# 2_STM32F107.net
KiCad netlist of a schematic drawn in Altium Designer
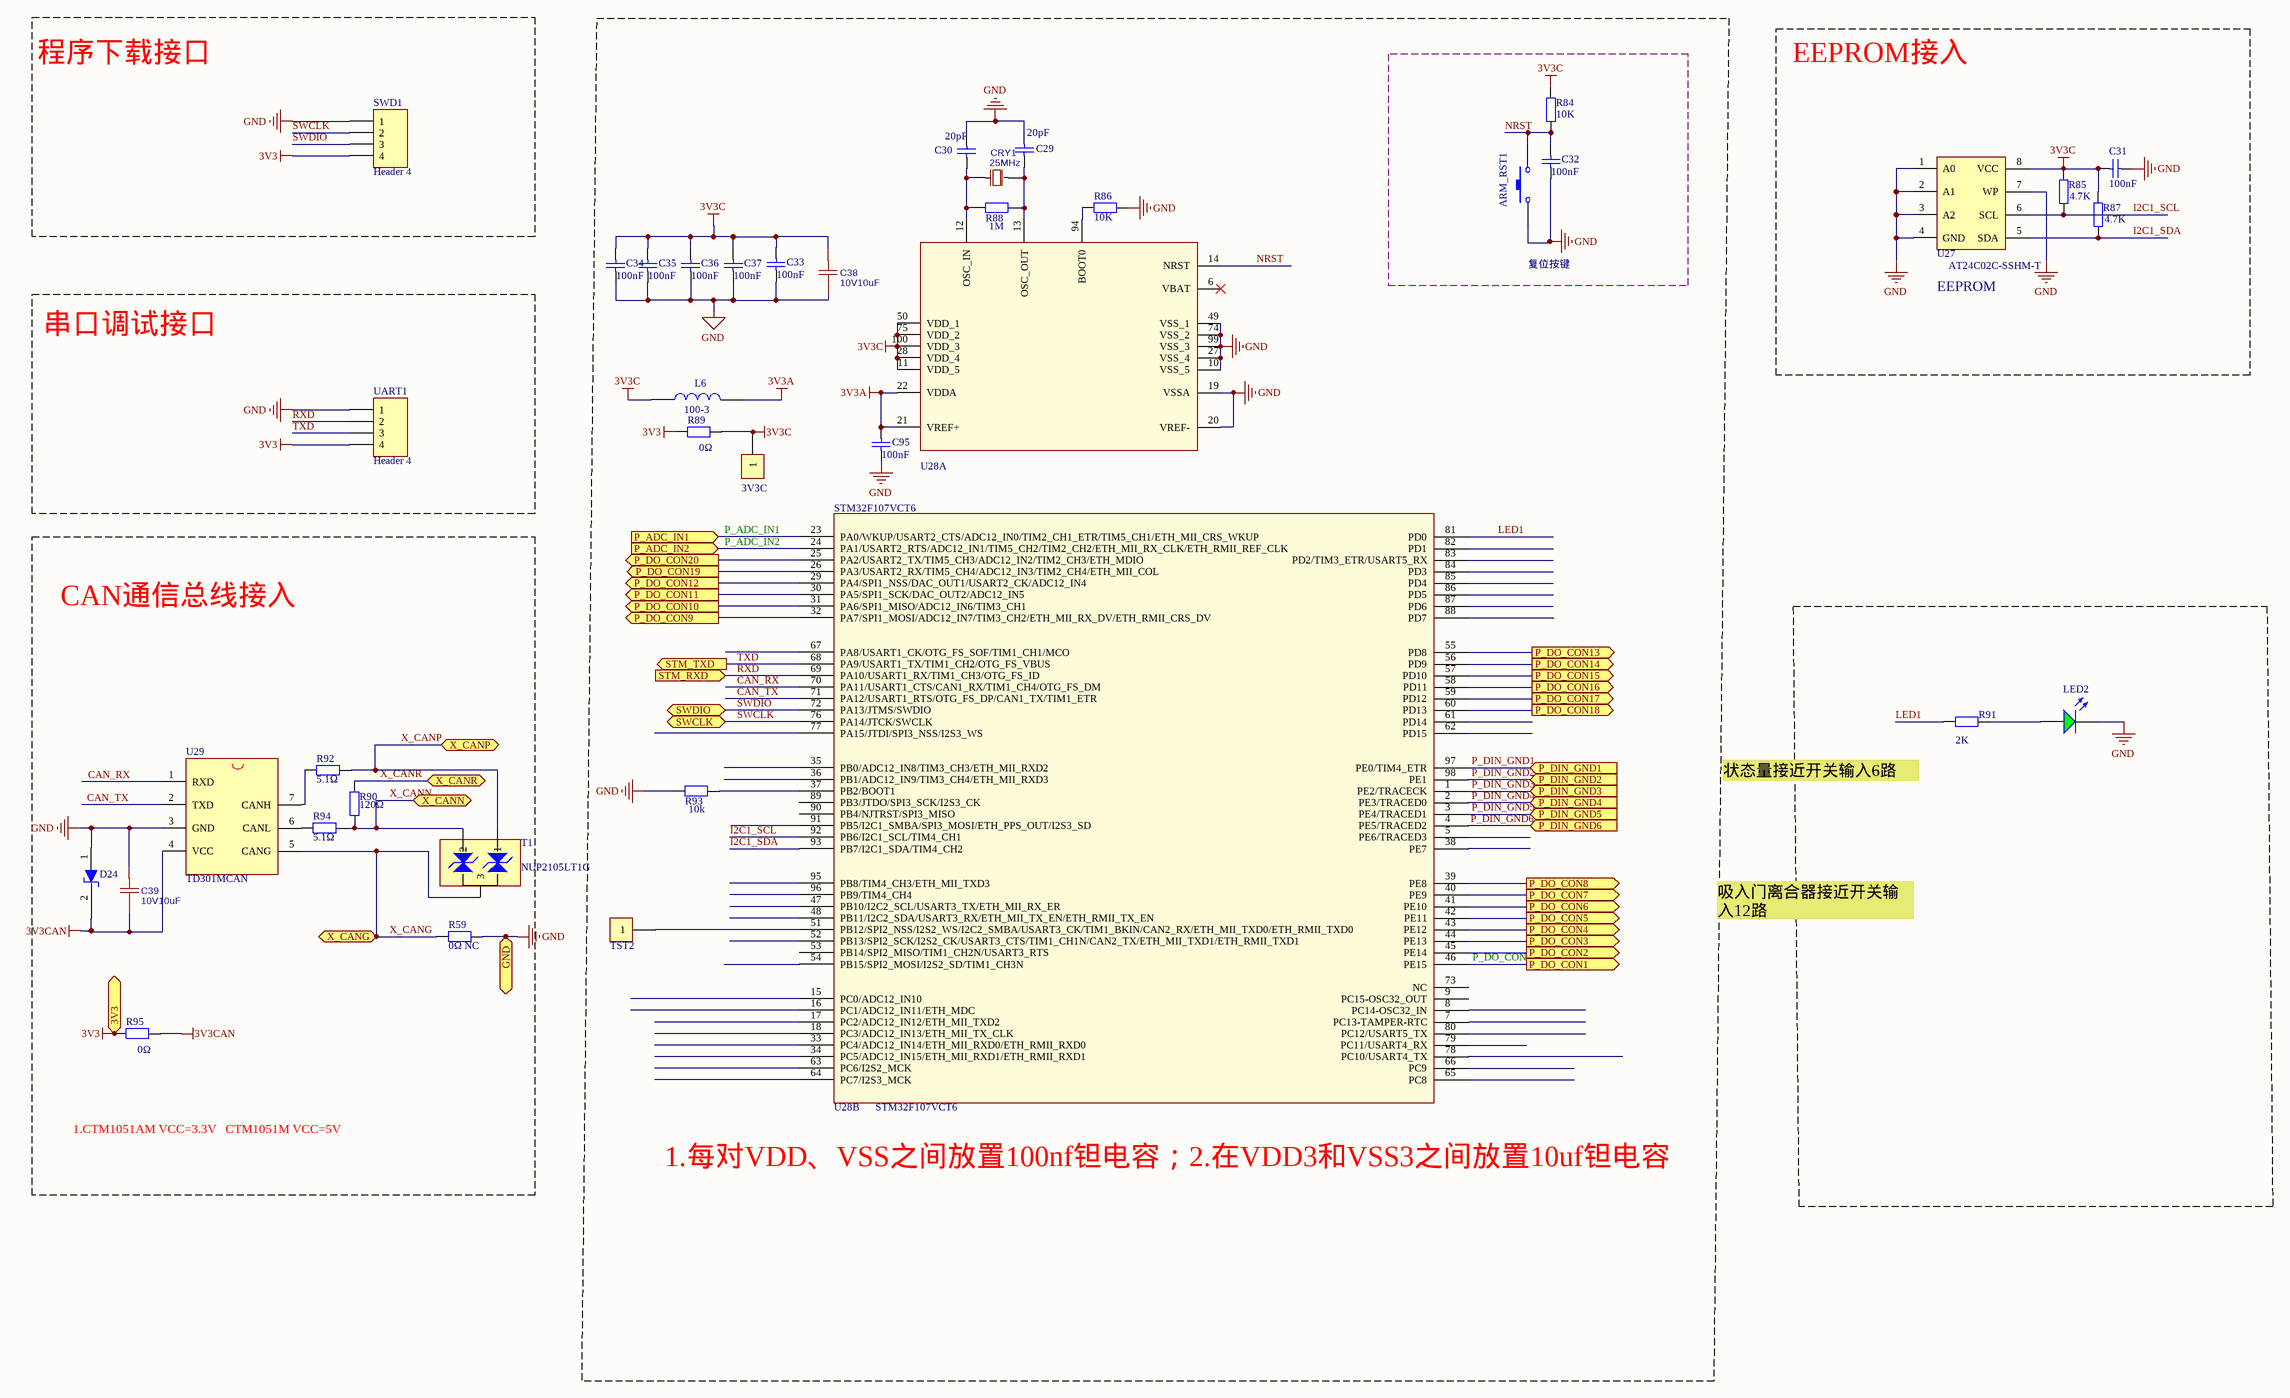
[diagram p0: 2.STM32F107.SchDoc]

(export (version "E")
  (design (tool "Eeschema 10.0.6"))
  (components
    (comp (ref "3V3C")
      (value "TST3V3C")
      (footprint "Con-TEST-VCC")
      (description "Connector")
      (libsource (lib "*") (part "CON1"))
    )
    (comp (ref "ARM_RST1")
      (value "button")
      (footprint "SW_PB2_A1")
      (description "轻触开关3.6*6.1*2.5")
      (libsource (lib "SUPERWDS") (part "button"))
    )
    (comp (ref "C29")
      (value "20pF")
      (footprint "C0603-M")
      (description "Capacitor")
      (fields (field (name "PUBLISHER") "Altium Limited"))
      (libsource (lib "SUPERWDS") (part "Cap1"))
    )
    (comp (ref "C30")
      (value "20pF")
      (footprint "C0603-M")
      (description "Capacitor")
      (fields (field (name "PUBLISHER") "Altium Limited"))
      (libsource (lib "SUPERWDS") (part "Cap1"))
    )
    (comp (ref "C31")
      (value "100nF")
      (footprint "C0603-M")
      (description "Capacitor")
      (fields (field (name "PUBLISHER") "Altium Limited"))
      (libsource (lib "SUPERWDS") (part "Cap1"))
    )
    (comp (ref "C32")
      (value "100nF")
      (footprint "C0603-M")
      (description "Capacitor")
      (fields (field (name "PUBLISHER") "Altium Limited"))
      (libsource (lib "SUPERWDS") (part "Cap1"))
    )
    (comp (ref "C33")
      (value "100nF")
      (footprint "C0603-M")
      (description "Capacitor")
      (fields (field (name "PUBLISHER") "Altium Limited"))
      (libsource (lib "SUPERWDS") (part "Cap1"))
    )
    (comp (ref "C34")
      (value "100nF")
      (footprint "C0603-M")
      (description "Capacitor")
      (fields (field (name "PUBLISHER") "Altium Limited"))
      (libsource (lib "SUPERWDS") (part "Cap1"))
    )
    (comp (ref "C35")
      (value "100nF")
      (footprint "C0603-M")
      (description "Capacitor")
      (fields (field (name "PUBLISHER") "Altium Limited"))
      (libsource (lib "SUPERWDS") (part "Cap1"))
    )
    (comp (ref "C36")
      (value "100nF")
      (footprint "C0603-M")
      (description "Capacitor")
      (fields (field (name "PUBLISHER") "Altium Limited"))
      (libsource (lib "SUPERWDS") (part "Cap1"))
    )
    (comp (ref "C37")
      (value "100nF")
      (footprint "C0603-M")
      (description "Capacitor")
      (fields (field (name "PUBLISHER") "Altium Limited"))
      (libsource (lib "SUPERWDS") (part "Cap1"))
    )
    (comp (ref "C38")
      (value "10V10uF")
      (footprint "C0603-M")
      (description "贴片电容")
      (fields
        (field (name "BOM_MANUFACTURER PART") "CL10A106KP8NNNC")
        (field (name "BOM_SUPPLIER PART") "C19702")
      )
      (libsource (lib "altium-import") (part "root_1_10uF_"))
    )
    (comp (ref "C39")
      (value "10V10uF")
      (footprint "C0603-M")
      (description "贴片电容")
      (fields
        (field (name "BOM_MANUFACTURER PART") "CL10A106KP8NNNC")
        (field (name "BOM_SUPPLIER PART") "C19702")
      )
      (libsource (lib "altium-import") (part "root_1_10uF_"))
    )
    (comp (ref "C95")
      (value "100nF")
      (footprint "C0603-M")
      (description "Capacitor")
      (fields (field (name "PUBLISHER") "Altium Limited"))
      (libsource (lib "SUPERWDS") (part "Cap1"))
    )
    (comp (ref "CRY1")
      (value "25MHz")
      (footprint "CRYSTAL-SMD_L11.5-W4.8-LS12.7")
      (fields
        (field (name "BOM_MANUFACTURER PART") "X49SM25MSD2SC")
        (field (name "BOM_SUPPLIER PART") "C14872")
      )
      (libsource (lib "altium-import") (part "root_0_25MHz_"))
    )
    (comp (ref "D24")
      (value "P6SMB6.8CA")
      (footprint "LC-SMA(DO-214AC)_S2")
      (description "TVS二极管/P6SMB6.8CA")
      (libsource (lib "自动对行") (part "TVS"))
    )
    (comp (ref "L6")
      (value "100-3")
      (footprint "L0805-M")
      (description "贴片磁珠/100Ω 3A/0805")
      (libsource (lib "*") (part "INDUCTOR"))
    )
    (comp (ref "LED2")
      (value "绿灯 0603")
      (footprint "0603_LED_S1")
      (description "发光二极管")
      (libsource (lib "Miscellaneous Devices LC") (part "0603 绿灯"))
    )
    (comp (ref "R59")
      (value "0Ω NC")
      (footprint "R0603-M")
      (description "Resistor")
      (fields (field (name "PUBLISHER") "Altium Limited"))
      (libsource (lib "") (part "Res2_3"))
    )
    (comp (ref "R84")
      (value "10K")
      (footprint "R0603-M")
      (description "Resistor")
      (fields (field (name "PUBLISHER") "Altium Limited"))
      (libsource (lib "SUPERWDS") (part "RES"))
    )
    (comp (ref "R85")
      (value "4.7K")
      (footprint "R0603-M")
      (description "Resistor")
      (fields (field (name "PUBLISHER") "Altium Limited"))
      (libsource (lib "SUPERWDS") (part "RES"))
    )
    (comp (ref "R86")
      (value "10K")
      (footprint "R0603-M")
      (description "Resistor")
      (fields (field (name "PUBLISHER") "Altium Limited"))
      (libsource (lib "") (part "RES_1"))
    )
    (comp (ref "R87")
      (value "4.7K")
      (footprint "R0603-M")
      (description "Resistor")
      (fields (field (name "PUBLISHER") "Altium Limited"))
      (libsource (lib "SUPERWDS") (part "RES"))
    )
    (comp (ref "R88")
      (value "1M")
      (footprint "R0603-M")
      (description "Resistor")
      (fields (field (name "PUBLISHER") "Altium Limited"))
      (libsource (lib "") (part "RES_1"))
    )
    (comp (ref "R89")
      (value "0Ω")
      (footprint "R0603-M")
      (description "Resistor")
      (fields (field (name "PUBLISHER") "Altium Limited"))
      (libsource (lib "") (part "Res2_1"))
    )
    (comp (ref "R90")
      (value "120Ω")
      (footprint "R0603-M")
      (description "贴片电阻/120Ω")
      (fields (field (name "PUBLISHER") "Altium Limited"))
      (libsource (lib "Miscellaneous Devices") (part "Res2"))
    )
    (comp (ref "R91")
      (value "2K")
      (footprint "R0603-M")
      (description "Resistor")
      (fields (field (name "PUBLISHER") "Altium Limited"))
      (libsource (lib "") (part "RES_2"))
    )
    (comp (ref "R92")
      (value "5.1Ω")
      (footprint "R0603-M")
      (description "贴片电阻/120Ω")
      (fields (field (name "PUBLISHER") "Altium Limited"))
      (libsource (lib "") (part "Res2_2"))
    )
    (comp (ref "R93")
      (value "10k")
      (footprint "R0603-M")
      (description "Resistor")
      (fields (field (name "PUBLISHER") "Altium Limited"))
      (libsource (lib "") (part "RES_1"))
    )
    (comp (ref "R94")
      (value "5.1Ω")
      (footprint "R0603-M")
      (description "贴片电阻/120Ω")
      (fields (field (name "PUBLISHER") "Altium Limited"))
      (libsource (lib "") (part "Res2_2"))
    )
    (comp (ref "R95")
      (value "0Ω")
      (footprint "R0603-M")
      (description "Resistor")
      (fields (field (name "PUBLISHER") "Altium Limited"))
      (libsource (lib "") (part "Res2_1"))
    )
    (comp (ref "SWD1")
      (value "Header 4")
      (footprint "HDR1X4")
      (description "Header, 4-Pin")
      (fields (field (name "PUBLISHER") "Altium Limited"))
      (libsource (lib "Miscellaneous Connectors") (part "Header 4"))
    )
    (comp (ref "T1")
      (value "NUP2105LT1G")
      (footprint "LC-SOT-23(SOT-23-3)")
      (description "TVS")
      (libsource (lib "motorCtr1") (part "TVS2"))
    )
    (comp (ref "TST2")
      (value "TST3V3A")
      (footprint "Con-TEST-VCC")
      (description "Connector")
      (libsource (lib "") (part "CON1_1"))
    )
    (comp (ref "U27")
      (value "AT24C02C-SSHM-T")
      (footprint "SO-8")
      (description "EEPROM")
      (libsource (lib "SUPERWDS") (part "AT24LC02"))
    )
    (comp (ref "U28")
      (value "STM32F107VCT6")
      (footprint "myPcb:LQFP100")
      (fields (field (name "ALTIUM_VALUE") "STM32F107VCT6"))
      (libsource (lib "SUPERWDS") (part "STM32F107"))
    )
    (comp (ref "U29")
      (value "TD301MCAN")
      (footprint "LC-DIP-8")
      (description "隔离CAN收发器CTM1051AM或TD301MCAN")
      (libsource (lib "YYGB") (part "CTM1051AM"))
    )
    (comp (ref "UART1")
      (value "Header 4")
      (footprint "HDR1X4")
      (description "Header, 4-Pin")
      (fields (field (name "PUBLISHER") "Altium Limited"))
      (libsource (lib "Miscellaneous Connectors") (part "Header 4"))
    )
  )
  (nets
    (net (code "2") (name "/CAN_RX") (class "Default")
      (node (ref "U28") (pin "70") (pinfunction "PA11/USART1_CTS/CAN1_RX/TIM1_CH4/OTG_FS_DM_70") (pintype "passive"))
      (node (ref "U29") (pin "1") (pinfunction "RXD_1") (pintype "passive"))
    )
    (net (code "3") (name "/CAN_TX") (class "Default")
      (node (ref "U28") (pin "71") (pinfunction "PA12/USART1_RTS/OTG_FS_DP/CAN1_TX/TIM1_ETR_71") (pintype "passive"))
      (node (ref "U29") (pin "2") (pinfunction "TXD_2") (pintype "passive"))
    )
    (net (code "4") (name "/I2C1_SCL") (class "Default")
      (node (ref "R85") (pin "1") (pinfunction "1_1") (pintype "passive"))
      (node (ref "U27") (pin "6") (pinfunction "SCL_6") (pintype "passive"))
      (node (ref "U28") (pin "92") (pinfunction "PB6/I2C1_SCL/TIM4_CH1_92") (pintype "passive"))
    )
    (net (code "5") (name "/I2C1_SDA") (class "Default")
      (node (ref "R87") (pin "1") (pinfunction "1_1") (pintype "passive"))
      (node (ref "U27") (pin "5") (pinfunction "SDA_5") (pintype "passive"))
      (node (ref "U28") (pin "93") (pinfunction "PB7/I2C1_SDA/TIM4_CH2_93") (pintype "passive"))
    )
    (net (code "6") (name "/LED1") (class "Default")
      (node (ref "R91") (pin "1") (pinfunction "1_1") (pintype "passive"))
      (node (ref "U28") (pin "81") (pinfunction "PD0_81") (pintype "passive"))
    )
    (net (code "7") (name "/NRST") (class "Default")
      (node (ref "ARM_RST1") (pin "2") (pinfunction "2_2") (pintype "passive"))
      (node (ref "C32") (pin "2") (pinfunction "2_2") (pintype "passive"))
      (node (ref "R84") (pin "1") (pinfunction "1_1") (pintype "passive"))
      (node (ref "U28") (pin "14") (pinfunction "NRST_14") (pintype "passive"))
    )
    (net (code "8") (name "/P_ADC_IN1") (class "Default")
      (node (ref "U28") (pin "23") (pinfunction "PA0/WKUP/USART2_CTS/ADC12_IN0/TIM2_CH1_ETR/TIM5_CH1/ETH_MII_CRS_WKUP_23") (pintype "passive"))
    )
    (net (code "9") (name "/P_ADC_IN2") (class "Default")
      (node (ref "U28") (pin "24") (pinfunction "PA1/USART2_RTS/ADC12_IN1/TIM5_CH2/TIM2_CH2/ETH_MII_RX_CLK/ETH_RMII_REF_CLK_24") (pintype "passive"))
    )
    (net (code "10") (name "/P_DIN_GND1") (class "Default")
      (node (ref "U28") (pin "97") (pinfunction "PE0/TIM4_ETR_97") (pintype "passive"))
    )
    (net (code "11") (name "/P_DIN_GND2") (class "Default")
      (node (ref "U28") (pin "98") (pinfunction "PE1_98") (pintype "passive"))
    )
    (net (code "12") (name "/P_DIN_GND3") (class "Default")
      (node (ref "U28") (pin "1") (pinfunction "PE2/TRACECK_1") (pintype "passive"))
    )
    (net (code "13") (name "/P_DIN_GND4") (class "Default")
      (node (ref "U28") (pin "2") (pinfunction "PE3/TRACED0_2") (pintype "passive"))
    )
    (net (code "14") (name "/P_DIN_GND5") (class "Default")
      (node (ref "U28") (pin "3") (pinfunction "PE4/TRACED1_3") (pintype "passive"))
    )
    (net (code "15") (name "/P_DIN_GND6") (class "Default")
      (node (ref "U28") (pin "4") (pinfunction "PE5/TRACED2_4") (pintype "passive"))
    )
    (net (code "16") (name "/P_DO_CON1") (class "Default")
      (node (ref "U28") (pin "46") (pinfunction "PE15_46") (pintype "passive"))
    )
    (net (code "17") (name "/P_DO_CON2") (class "Default")
      (node (ref "U28") (pin "45") (pinfunction "PE14_45") (pintype "passive"))
    )
    (net (code "18") (name "/P_DO_CON3") (class "Default")
      (node (ref "U28") (pin "44") (pinfunction "PE13_44") (pintype "passive"))
    )
    (net (code "19") (name "/P_DO_CON4") (class "Default")
      (node (ref "U28") (pin "43") (pinfunction "PE12_43") (pintype "passive"))
    )
    (net (code "20") (name "/P_DO_CON5") (class "Default")
      (node (ref "U28") (pin "42") (pinfunction "PE11_42") (pintype "passive"))
    )
    (net (code "21") (name "/P_DO_CON6") (class "Default")
      (node (ref "U28") (pin "41") (pinfunction "PE10_41") (pintype "passive"))
    )
    (net (code "22") (name "/P_DO_CON7") (class "Default")
      (node (ref "U28") (pin "40") (pinfunction "PE9_40") (pintype "passive"))
    )
    (net (code "23") (name "/P_DO_CON8") (class "Default")
      (node (ref "U28") (pin "39") (pinfunction "PE8_39") (pintype "passive"))
    )
    (net (code "24") (name "/P_DO_CON9") (class "Default")
      (node (ref "U28") (pin "32") (pinfunction "PA7/SPI1_MOSI/ADC12_IN7/TIM3_CH2/ETH_MII_RX_DV/ETH_RMII_CRS_DV_32") (pintype "passive"))
    )
    (net (code "25") (name "/P_DO_CON10") (class "Default")
      (node (ref "U28") (pin "31") (pinfunction "PA6/SPI1_MISO/ADC12_IN6/TIM3_CH1_31") (pintype "passive"))
    )
    (net (code "26") (name "/P_DO_CON11") (class "Default")
      (node (ref "U28") (pin "30") (pinfunction "PA5/SPI1_SCK/DAC_OUT2/ADC12_IN5_30") (pintype "passive"))
    )
    (net (code "27") (name "/P_DO_CON12") (class "Default")
      (node (ref "U28") (pin "29") (pinfunction "PA4/SPI1_NSS/DAC_OUT1/USART2_CK/ADC12_IN4_29") (pintype "passive"))
    )
    (net (code "28") (name "/P_DO_CON13") (class "Default")
      (node (ref "U28") (pin "55") (pinfunction "PD8_55") (pintype "passive"))
    )
    (net (code "29") (name "/P_DO_CON14") (class "Default")
      (node (ref "U28") (pin "56") (pinfunction "PD9_56") (pintype "passive"))
    )
    (net (code "30") (name "/P_DO_CON15") (class "Default")
      (node (ref "U28") (pin "57") (pinfunction "PD10_57") (pintype "passive"))
    )
    (net (code "31") (name "/P_DO_CON16") (class "Default")
      (node (ref "U28") (pin "58") (pinfunction "PD11_58") (pintype "passive"))
    )
    (net (code "32") (name "/P_DO_CON17") (class "Default")
      (node (ref "U28") (pin "59") (pinfunction "PD12_59") (pintype "passive"))
    )
    (net (code "33") (name "/P_DO_CON18") (class "Default")
      (node (ref "U28") (pin "60") (pinfunction "PD13_60") (pintype "passive"))
    )
    (net (code "34") (name "/P_DO_CON19") (class "Default")
      (node (ref "U28") (pin "26") (pinfunction "PA3/USART2_RX/TIM5_CH4/ADC12_IN3/TIM2_CH4/ETH_MII_COL_26") (pintype "passive"))
    )
    (net (code "35") (name "/P_DO_CON20") (class "Default")
      (node (ref "U28") (pin "25") (pinfunction "PA2/USART2_TX/TIM5_CH3/ADC12_IN2/TIM2_CH3/ETH_MDIO_25") (pintype "passive"))
    )
    (net (code "36") (name "/RXD") (class "Default")
      (node (ref "U28") (pin "69") (pinfunction "PA10/USART1_RX/TIM1_CH3/OTG_FS_ID_69") (pintype "passive"))
      (node (ref "UART1") (pin "2") (pinfunction "2_2") (pintype "passive"))
    )
    (net (code "37") (name "/SWCLK") (class "Default")
      (node (ref "SWD1") (pin "2") (pinfunction "2_2") (pintype "passive"))
      (node (ref "U28") (pin "76") (pinfunction "PA14/JTCK/SWCLK_76") (pintype "passive"))
    )
    (net (code "38") (name "/SWDIO") (class "Default")
      (node (ref "SWD1") (pin "3") (pinfunction "3_3") (pintype "passive"))
      (node (ref "U28") (pin "72") (pinfunction "PA13/JTMS/SWDIO_72") (pintype "passive"))
    )
    (net (code "39") (name "/TXD") (class "Default")
      (node (ref "U28") (pin "68") (pinfunction "PA9/USART1_TX/TIM1_CH2/OTG_FS_VBUS_68") (pintype "passive"))
      (node (ref "UART1") (pin "3") (pinfunction "3_3") (pintype "passive"))
    )
    (net (code "40") (name "/X_CANG") (class "Default")
      (node (ref "R59") (pin "2") (pinfunction "2_2") (pintype "passive"))
      (node (ref "T1") (pin "3") (pinfunction "3_3") (pintype "passive"))
      (node (ref "U29") (pin "5") (pinfunction "CANG_5") (pintype "passive"))
    )
    (net (code "41") (name "/X_CANN") (class "Default")
      (node (ref "R90") (pin "2") (pinfunction "2_2") (pintype "passive"))
      (node (ref "R94") (pin "1") (pinfunction "1_1") (pintype "passive"))
      (node (ref "T1") (pin "2") (pinfunction "2_2") (pintype "passive"))
    )
    (net (code "42") (name "/X_CANP") (class "Default")
      (node (ref "R92") (pin "1") (pinfunction "1_1") (pintype "passive"))
      (node (ref "T1") (pin "1") (pinfunction "1_1") (pintype "passive"))
    )
    (net (code "43") (name "/X_CANR") (class "Default")
      (node (ref "R90") (pin "1") (pinfunction "1_1") (pintype "passive"))
    )
    (net (code "44") (name "3V3") (class "Default")
      (node (ref "R89") (pin "1") (pinfunction "1_1") (pintype "passive"))
      (node (ref "R95") (pin "1") (pinfunction "1_1") (pintype "passive"))
      (node (ref "SWD1") (pin "4") (pinfunction "4_4") (pintype "passive"))
      (node (ref "UART1") (pin "4") (pinfunction "4_4") (pintype "passive"))
    )
    (net (code "45") (name "3V3A") (class "Default")
      (node (ref "C95") (pin "2") (pinfunction "2_2") (pintype "passive"))
      (node (ref "L6") (pin "2") (pinfunction "2_2") (pintype "passive"))
      (node (ref "U28") (pin "21") (pinfunction "VREF+_21") (pintype "passive"))
      (node (ref "U28") (pin "22") (pinfunction "VDDA_22") (pintype "passive"))
    )
    (net (code "46") (name "3V3C") (class "Default")
      (node (ref "3V3C") (pin "1") (pinfunction "1_1") (pintype "passive"))
      (node (ref "C31") (pin "2") (pinfunction "2_2") (pintype "passive"))
      (node (ref "C33") (pin "2") (pinfunction "2_2") (pintype "passive"))
      (node (ref "C34") (pin "2") (pinfunction "2_2") (pintype "passive"))
      (node (ref "C35") (pin "2") (pinfunction "2_2") (pintype "passive"))
      (node (ref "C36") (pin "2") (pinfunction "2_2") (pintype "passive"))
      (node (ref "C37") (pin "2") (pinfunction "2_2") (pintype "passive"))
      (node (ref "C38") (pin "2") (pinfunction "2_2") (pintype "passive"))
      (node (ref "L6") (pin "1") (pinfunction "1_1") (pintype "passive"))
      (node (ref "R84") (pin "2") (pinfunction "2_2") (pintype "passive"))
      (node (ref "R85") (pin "2") (pinfunction "2_2") (pintype "passive"))
      (node (ref "R87") (pin "2") (pinfunction "2_2") (pintype "passive"))
      (node (ref "R89") (pin "2") (pinfunction "2_2") (pintype "passive"))
      (node (ref "U27") (pin "8") (pinfunction "VCC_8") (pintype "passive"))
      (node (ref "U28") (pin "100") (pinfunction "VDD_3_100") (pintype "passive"))
      (node (ref "U28") (pin "11") (pinfunction "VDD_5_11") (pintype "passive"))
      (node (ref "U28") (pin "28") (pinfunction "VDD_4_28") (pintype "passive"))
      (node (ref "U28") (pin "50") (pinfunction "VDD_1_50") (pintype "passive"))
      (node (ref "U28") (pin "75") (pinfunction "VDD_2_75") (pintype "passive"))
    )
    (net (code "47") (name "3V3CAN") (class "Default")
      (node (ref "C39") (pin "1") (pinfunction "1_1") (pintype "passive"))
      (node (ref "D24") (pin "2") (pinfunction "2_2") (pintype "passive"))
      (node (ref "R95") (pin "2") (pinfunction "2_2") (pintype "passive"))
      (node (ref "U29") (pin "4") (pinfunction "VCC_4") (pintype "passive"))
    )
    (net (code "48") (name "GND") (class "Default")
      (node (ref "ARM_RST1") (pin "1") (pinfunction "1_1") (pintype "passive"))
      (node (ref "C29") (pin "1") (pinfunction "1_1") (pintype "passive"))
      (node (ref "C30") (pin "2") (pinfunction "2_2") (pintype "passive"))
      (node (ref "C31") (pin "1") (pinfunction "1_1") (pintype "passive"))
      (node (ref "C32") (pin "1") (pinfunction "1_1") (pintype "passive"))
      (node (ref "C33") (pin "1") (pinfunction "1_1") (pintype "passive"))
      (node (ref "C34") (pin "1") (pinfunction "1_1") (pintype "passive"))
      (node (ref "C35") (pin "1") (pinfunction "1_1") (pintype "passive"))
      (node (ref "C36") (pin "1") (pinfunction "1_1") (pintype "passive"))
      (node (ref "C37") (pin "1") (pinfunction "1_1") (pintype "passive"))
      (node (ref "C38") (pin "1") (pinfunction "1_1") (pintype "passive"))
      (node (ref "C39") (pin "2") (pinfunction "2_2") (pintype "passive"))
      (node (ref "C95") (pin "1") (pinfunction "1_1") (pintype "passive"))
      (node (ref "D24") (pin "1") (pinfunction "1_1") (pintype "passive"))
      (node (ref "LED2") (pin "K") (pinfunction "K_K") (pintype "passive"))
      (node (ref "R59") (pin "1") (pinfunction "1_1") (pintype "passive"))
      (node (ref "R86") (pin "1") (pinfunction "1_1") (pintype "passive"))
      (node (ref "R93") (pin "2") (pinfunction "2_2") (pintype "passive"))
      (node (ref "SWD1") (pin "1") (pinfunction "1_1") (pintype "passive"))
      (node (ref "U27") (pin "1") (pinfunction "A0_1") (pintype "passive"))
      (node (ref "U27") (pin "2") (pinfunction "A1_2") (pintype "passive"))
      (node (ref "U27") (pin "3") (pinfunction "A2_3") (pintype "passive"))
      (node (ref "U27") (pin "4") (pinfunction "GND_4") (pintype "passive"))
      (node (ref "U27") (pin "7") (pinfunction "WP_7") (pintype "passive"))
      (node (ref "U28") (pin "10") (pinfunction "VSS_5_10") (pintype "passive"))
      (node (ref "U28") (pin "19") (pinfunction "VSSA_19") (pintype "passive"))
      (node (ref "U28") (pin "20") (pinfunction "VREF-_20") (pintype "passive"))
      (node (ref "U28") (pin "27") (pinfunction "VSS_4_27") (pintype "passive"))
      (node (ref "U28") (pin "49") (pinfunction "VSS_1_49") (pintype "passive"))
      (node (ref "U28") (pin "74") (pinfunction "VSS_2_74") (pintype "passive"))
      (node (ref "U28") (pin "99") (pinfunction "VSS_3_99") (pintype "passive"))
      (node (ref "U29") (pin "3") (pinfunction "GND_3") (pintype "passive"))
      (node (ref "UART1") (pin "1") (pinfunction "1_1") (pintype "passive"))
    )
    (net (code "49") (name "Net-(CRY1-OSC1)") (class "Default")
      (node (ref "C30") (pin "1") (pinfunction "1_1") (pintype "passive"))
      (node (ref "CRY1") (pin "1") (pinfunction "OSC1_1") (pintype "passive"))
      (node (ref "R88") (pin "2") (pinfunction "2_2") (pintype "passive"))
      (node (ref "U28") (pin "12") (pinfunction "OSC_IN_12") (pintype "passive"))
    )
    (net (code "50") (name "Net-(CRY1-OSC2)") (class "Default")
      (node (ref "C29") (pin "2") (pinfunction "2_2") (pintype "passive"))
      (node (ref "CRY1") (pin "2") (pinfunction "OSC2_2") (pintype "passive"))
      (node (ref "R88") (pin "1") (pinfunction "1_1") (pintype "passive"))
      (node (ref "U28") (pin "13") (pinfunction "OSC_OUT_13") (pintype "passive"))
    )
    (net (code "51") (name "Net-(LED2-PadA)") (class "Default")
      (node (ref "LED2") (pin "A") (pinfunction "A_A") (pintype "passive"))
      (node (ref "R91") (pin "2") (pinfunction "2_2") (pintype "passive"))
    )
    (net (code "52") (name "Net-(U28A-BOOT0)") (class "Default")
      (node (ref "R86") (pin "2") (pinfunction "2_2") (pintype "passive"))
      (node (ref "U28") (pin "94") (pinfunction "BOOT0_94") (pintype "passive"))
    )
    (net (code "53") (name "Net-(U28B-PB2{slash}BOOT1)") (class "Default")
      (node (ref "R93") (pin "1") (pinfunction "1_1") (pintype "passive"))
      (node (ref "U28") (pin "37") (pinfunction "PB2/BOOT1_37") (pintype "passive"))
    )
    (net (code "54") (name "Net-(U28B-PB12{slash}SPI2_NSS{slash}I2S2_WS{slash}I2C2_SMBA{slash}USART3_CK{slash}TIM1_BKIN{slash}CAN2_RX{slash}ETH_MII_TXD0{slash}ETH_RMII_TXD0)") (class "Default")
      (node (ref "TST2") (pin "1") (pinfunction "1_1") (pintype "passive"))
      (node (ref "U28") (pin "51") (pinfunction "PB12/SPI2_NSS/I2S2_WS/I2C2_SMBA/USART3_CK/TIM1_BKIN/CAN2_RX/ETH_MII_TXD0/ETH_RMII_TXD0_51") (pintype "passive"))
    )
    (net (code "55") (name "Net-(U29-CANH)") (class "Default")
      (node (ref "R92") (pin "2") (pinfunction "2_2") (pintype "passive"))
      (node (ref "U29") (pin "7") (pinfunction "CANH_7") (pintype "passive"))
    )
    (net (code "56") (name "Net-(U29-CANL)") (class "Default")
      (node (ref "R94") (pin "2") (pinfunction "2_2") (pintype "passive"))
      (node (ref "U29") (pin "6") (pinfunction "CANL_6") (pintype "passive"))
    )
    (net (code "57") (name "unconnected-(U28A-VBAT-Pad6)") (class "Default")
      (node (ref "U28") (pin "6") (pinfunction "VBAT_6") (pintype "passive+no_connect"))
    )
    (net (code "58") (name "unconnected-(U28B-NC-Pad73)") (class "Default")
      (node (ref "U28") (pin "73") (pinfunction "NC_73") (pintype "passive"))
    )
    (net (code "59") (name "unconnected-(U28B-PA8{slash}USART1_CK{slash}OTG_FS_SOF{slash}TIM1_CH1{slash}MCO-Pad67)") (class "Default")
      (node (ref "U28") (pin "67") (pinfunction "PA8/USART1_CK/OTG_FS_SOF/TIM1_CH1/MCO_67") (pintype "passive"))
    )
    (net (code "60") (name "unconnected-(U28B-PA15{slash}JTDI{slash}SPI3_NSS{slash}I2S3_WS-Pad77)") (class "Default")
      (node (ref "U28") (pin "77") (pinfunction "PA15/JTDI/SPI3_NSS/I2S3_WS_77") (pintype "passive"))
    )
    (net (code "61") (name "unconnected-(U28B-PB0{slash}ADC12_IN8{slash}TIM3_CH3{slash}ETH_MII_RXD2-Pad35)") (class "Default")
      (node (ref "U28") (pin "35") (pinfunction "PB0/ADC12_IN8/TIM3_CH3/ETH_MII_RXD2_35") (pintype "passive"))
    )
    (net (code "62") (name "unconnected-(U28B-PB1{slash}ADC12_IN9{slash}TIM3_CH4{slash}ETH_MII_RXD3-Pad36)") (class "Default")
      (node (ref "U28") (pin "36") (pinfunction "PB1/ADC12_IN9/TIM3_CH4/ETH_MII_RXD3_36") (pintype "passive"))
    )
    (net (code "63") (name "unconnected-(U28B-PB3{slash}JTDO{slash}SPI3_SCK{slash}I2S3_CK-Pad89)") (class "Default")
      (node (ref "U28") (pin "89") (pinfunction "PB3/JTDO/SPI3_SCK/I2S3_CK_89") (pintype "passive"))
    )
    (net (code "64") (name "unconnected-(U28B-PB4{slash}NJTRST{slash}SPI3_MISO-Pad90)") (class "Default")
      (node (ref "U28") (pin "90") (pinfunction "PB4/NJTRST/SPI3_MISO_90") (pintype "passive"))
    )
    (net (code "65") (name "unconnected-(U28B-PB5{slash}I2C1_SMBA{slash}SPI3_MOSI{slash}ETH_PPS_OUT{slash}I2S3_SD-Pad91)") (class "Default")
      (node (ref "U28") (pin "91") (pinfunction "PB5/I2C1_SMBA/SPI3_MOSI/ETH_PPS_OUT/I2S3_SD_91") (pintype "passive"))
    )
    (net (code "66") (name "unconnected-(U28B-PB8{slash}TIM4_CH3{slash}ETH_MII_TXD3-Pad95)") (class "Default")
      (node (ref "U28") (pin "95") (pinfunction "PB8/TIM4_CH3/ETH_MII_TXD3_95") (pintype "passive"))
    )
    (net (code "67") (name "unconnected-(U28B-PB9{slash}TIM4_CH4-Pad96)") (class "Default")
      (node (ref "U28") (pin "96") (pinfunction "PB9/TIM4_CH4_96") (pintype "passive"))
    )
    (net (code "68") (name "unconnected-(U28B-PB10{slash}I2C2_SCL{slash}USART3_TX{slash}ETH_MII_RX_ER-Pad47)") (class "Default")
      (node (ref "U28") (pin "47") (pinfunction "PB10/I2C2_SCL/USART3_TX/ETH_MII_RX_ER_47") (pintype "passive"))
    )
    (net (code "69") (name "unconnected-(U28B-PB11{slash}I2C2_SDA{slash}USART3_RX{slash}ETH_MII_TX_EN{slash}ETH_RMII_TX_EN-Pad48)") (class "Default")
      (node (ref "U28") (pin "48") (pinfunction "PB11/I2C2_SDA/USART3_RX/ETH_MII_TX_EN/ETH_RMII_TX_EN_48") (pintype "passive"))
    )
    (net (code "70") (name "unconnected-(U28B-PB13{slash}SPI2_SCK{slash}I2S2_CK{slash}USART3_CTS{slash}TIM1_CH1N{slash}CAN2_TX{slash}ETH_MII_TXD1{slash}ETH_RMII_TXD1-Pad52)") (class "Default")
      (node (ref "U28") (pin "52") (pinfunction "PB13/SPI2_SCK/I2S2_CK/USART3_CTS/TIM1_CH1N/CAN2_TX/ETH_MII_TXD1/ETH_RMII_TXD1_52") (pintype "passive"))
    )
    (net (code "71") (name "unconnected-(U28B-PB14{slash}SPI2_MISO{slash}TIM1_CH2N{slash}USART3_RTS-Pad53)") (class "Default")
      (node (ref "U28") (pin "53") (pinfunction "PB14/SPI2_MISO/TIM1_CH2N/USART3_RTS_53") (pintype "passive"))
    )
    (net (code "72") (name "unconnected-(U28B-PB15{slash}SPI2_MOSI{slash}I2S2_SD{slash}TIM1_CH3N-Pad54)") (class "Default")
      (node (ref "U28") (pin "54") (pinfunction "PB15/SPI2_MOSI/I2S2_SD/TIM1_CH3N_54") (pintype "passive"))
    )
    (net (code "73") (name "unconnected-(U28B-PC0{slash}ADC12_IN10-Pad15)") (class "Default")
      (node (ref "U28") (pin "15") (pinfunction "PC0/ADC12_IN10_15") (pintype "passive"))
    )
    (net (code "74") (name "unconnected-(U28B-PC1{slash}ADC12_IN11{slash}ETH_MDC-Pad16)") (class "Default")
      (node (ref "U28") (pin "16") (pinfunction "PC1/ADC12_IN11/ETH_MDC_16") (pintype "passive"))
    )
    (net (code "75") (name "unconnected-(U28B-PC2{slash}ADC12_IN12{slash}ETH_MII_TXD2-Pad17)") (class "Default")
      (node (ref "U28") (pin "17") (pinfunction "PC2/ADC12_IN12/ETH_MII_TXD2_17") (pintype "passive"))
    )
    (net (code "76") (name "unconnected-(U28B-PC3{slash}ADC12_IN13{slash}ETH_MII_TX_CLK-Pad18)") (class "Default")
      (node (ref "U28") (pin "18") (pinfunction "PC3/ADC12_IN13/ETH_MII_TX_CLK_18") (pintype "passive"))
    )
    (net (code "77") (name "unconnected-(U28B-PC4{slash}ADC12_IN14{slash}ETH_MII_RXD0{slash}ETH_RMII_RXD0-Pad33)") (class "Default")
      (node (ref "U28") (pin "33") (pinfunction "PC4/ADC12_IN14/ETH_MII_RXD0/ETH_RMII_RXD0_33") (pintype "passive"))
    )
    (net (code "78") (name "unconnected-(U28B-PC5{slash}ADC12_IN15{slash}ETH_MII_RXD1{slash}ETH_RMII_RXD1-Pad34)") (class "Default")
      (node (ref "U28") (pin "34") (pinfunction "PC5/ADC12_IN15/ETH_MII_RXD1/ETH_RMII_RXD1_34") (pintype "passive"))
    )
    (net (code "79") (name "unconnected-(U28B-PC6{slash}I2S2_MCK-Pad63)") (class "Default")
      (node (ref "U28") (pin "63") (pinfunction "PC6/I2S2_MCK_63") (pintype "passive"))
    )
    (net (code "80") (name "unconnected-(U28B-PC7{slash}I2S3_MCK-Pad64)") (class "Default")
      (node (ref "U28") (pin "64") (pinfunction "PC7/I2S3_MCK_64") (pintype "passive"))
    )
    (net (code "81") (name "unconnected-(U28B-PC8-Pad65)") (class "Default")
      (node (ref "U28") (pin "65") (pinfunction "PC8_65") (pintype "passive"))
    )
    (net (code "82") (name "unconnected-(U28B-PC9-Pad66)") (class "Default")
      (node (ref "U28") (pin "66") (pinfunction "PC9_66") (pintype "passive"))
    )
    (net (code "83") (name "unconnected-(U28B-PC10{slash}USART4_TX-Pad78)") (class "Default")
      (node (ref "U28") (pin "78") (pinfunction "PC10/USART4_TX_78") (pintype "passive"))
    )
    (net (code "84") (name "unconnected-(U28B-PC11{slash}USART4_RX-Pad79)") (class "Default")
      (node (ref "U28") (pin "79") (pinfunction "PC11/USART4_RX_79") (pintype "passive"))
    )
    (net (code "85") (name "unconnected-(U28B-PC12{slash}USART5_TX-Pad80)") (class "Default")
      (node (ref "U28") (pin "80") (pinfunction "PC12/USART5_TX_80") (pintype "passive"))
    )
    (net (code "86") (name "unconnected-(U28B-PC13-TAMPER-RTC-Pad7)") (class "Default")
      (node (ref "U28") (pin "7") (pinfunction "PC13-TAMPER-RTC_7") (pintype "passive"))
    )
    (net (code "87") (name "unconnected-(U28B-PC14-OSC32_IN-Pad8)") (class "Default")
      (node (ref "U28") (pin "8") (pinfunction "PC14-OSC32_IN_8") (pintype "passive"))
    )
    (net (code "88") (name "unconnected-(U28B-PC15-OSC32_OUT-Pad9)") (class "Default")
      (node (ref "U28") (pin "9") (pinfunction "PC15-OSC32_OUT_9") (pintype "passive"))
    )
    (net (code "89") (name "unconnected-(U28B-PD1-Pad82)") (class "Default")
      (node (ref "U28") (pin "82") (pinfunction "PD1_82") (pintype "passive"))
    )
    (net (code "90") (name "unconnected-(U28B-PD2{slash}TIM3_ETR{slash}USART5_RX-Pad83)") (class "Default")
      (node (ref "U28") (pin "83") (pinfunction "PD2/TIM3_ETR/USART5_RX_83") (pintype "passive"))
    )
    (net (code "91") (name "unconnected-(U28B-PD3-Pad84)") (class "Default")
      (node (ref "U28") (pin "84") (pinfunction "PD3_84") (pintype "passive"))
    )
    (net (code "92") (name "unconnected-(U28B-PD4-Pad85)") (class "Default")
      (node (ref "U28") (pin "85") (pinfunction "PD4_85") (pintype "passive"))
    )
    (net (code "93") (name "unconnected-(U28B-PD5-Pad86)") (class "Default")
      (node (ref "U28") (pin "86") (pinfunction "PD5_86") (pintype "passive"))
    )
    (net (code "94") (name "unconnected-(U28B-PD6-Pad87)") (class "Default")
      (node (ref "U28") (pin "87") (pinfunction "PD6_87") (pintype "passive"))
    )
    (net (code "95") (name "unconnected-(U28B-PD7-Pad88)") (class "Default")
      (node (ref "U28") (pin "88") (pinfunction "PD7_88") (pintype "passive"))
    )
    (net (code "96") (name "unconnected-(U28B-PD14-Pad61)") (class "Default")
      (node (ref "U28") (pin "61") (pinfunction "PD14_61") (pintype "passive"))
    )
    (net (code "97") (name "unconnected-(U28B-PD15-Pad62)") (class "Default")
      (node (ref "U28") (pin "62") (pinfunction "PD15_62") (pintype "passive"))
    )
    (net (code "98") (name "unconnected-(U28B-PE6{slash}TRACED3-Pad5)") (class "Default")
      (node (ref "U28") (pin "5") (pinfunction "PE6/TRACED3_5") (pintype "passive"))
    )
    (net (code "99") (name "unconnected-(U28B-PE7-Pad38)") (class "Default")
      (node (ref "U28") (pin "38") (pinfunction "PE7_38") (pintype "passive"))
    )
  )
)
